# kicker.net
KiCad netlist of a schematic drawn in EAGLE
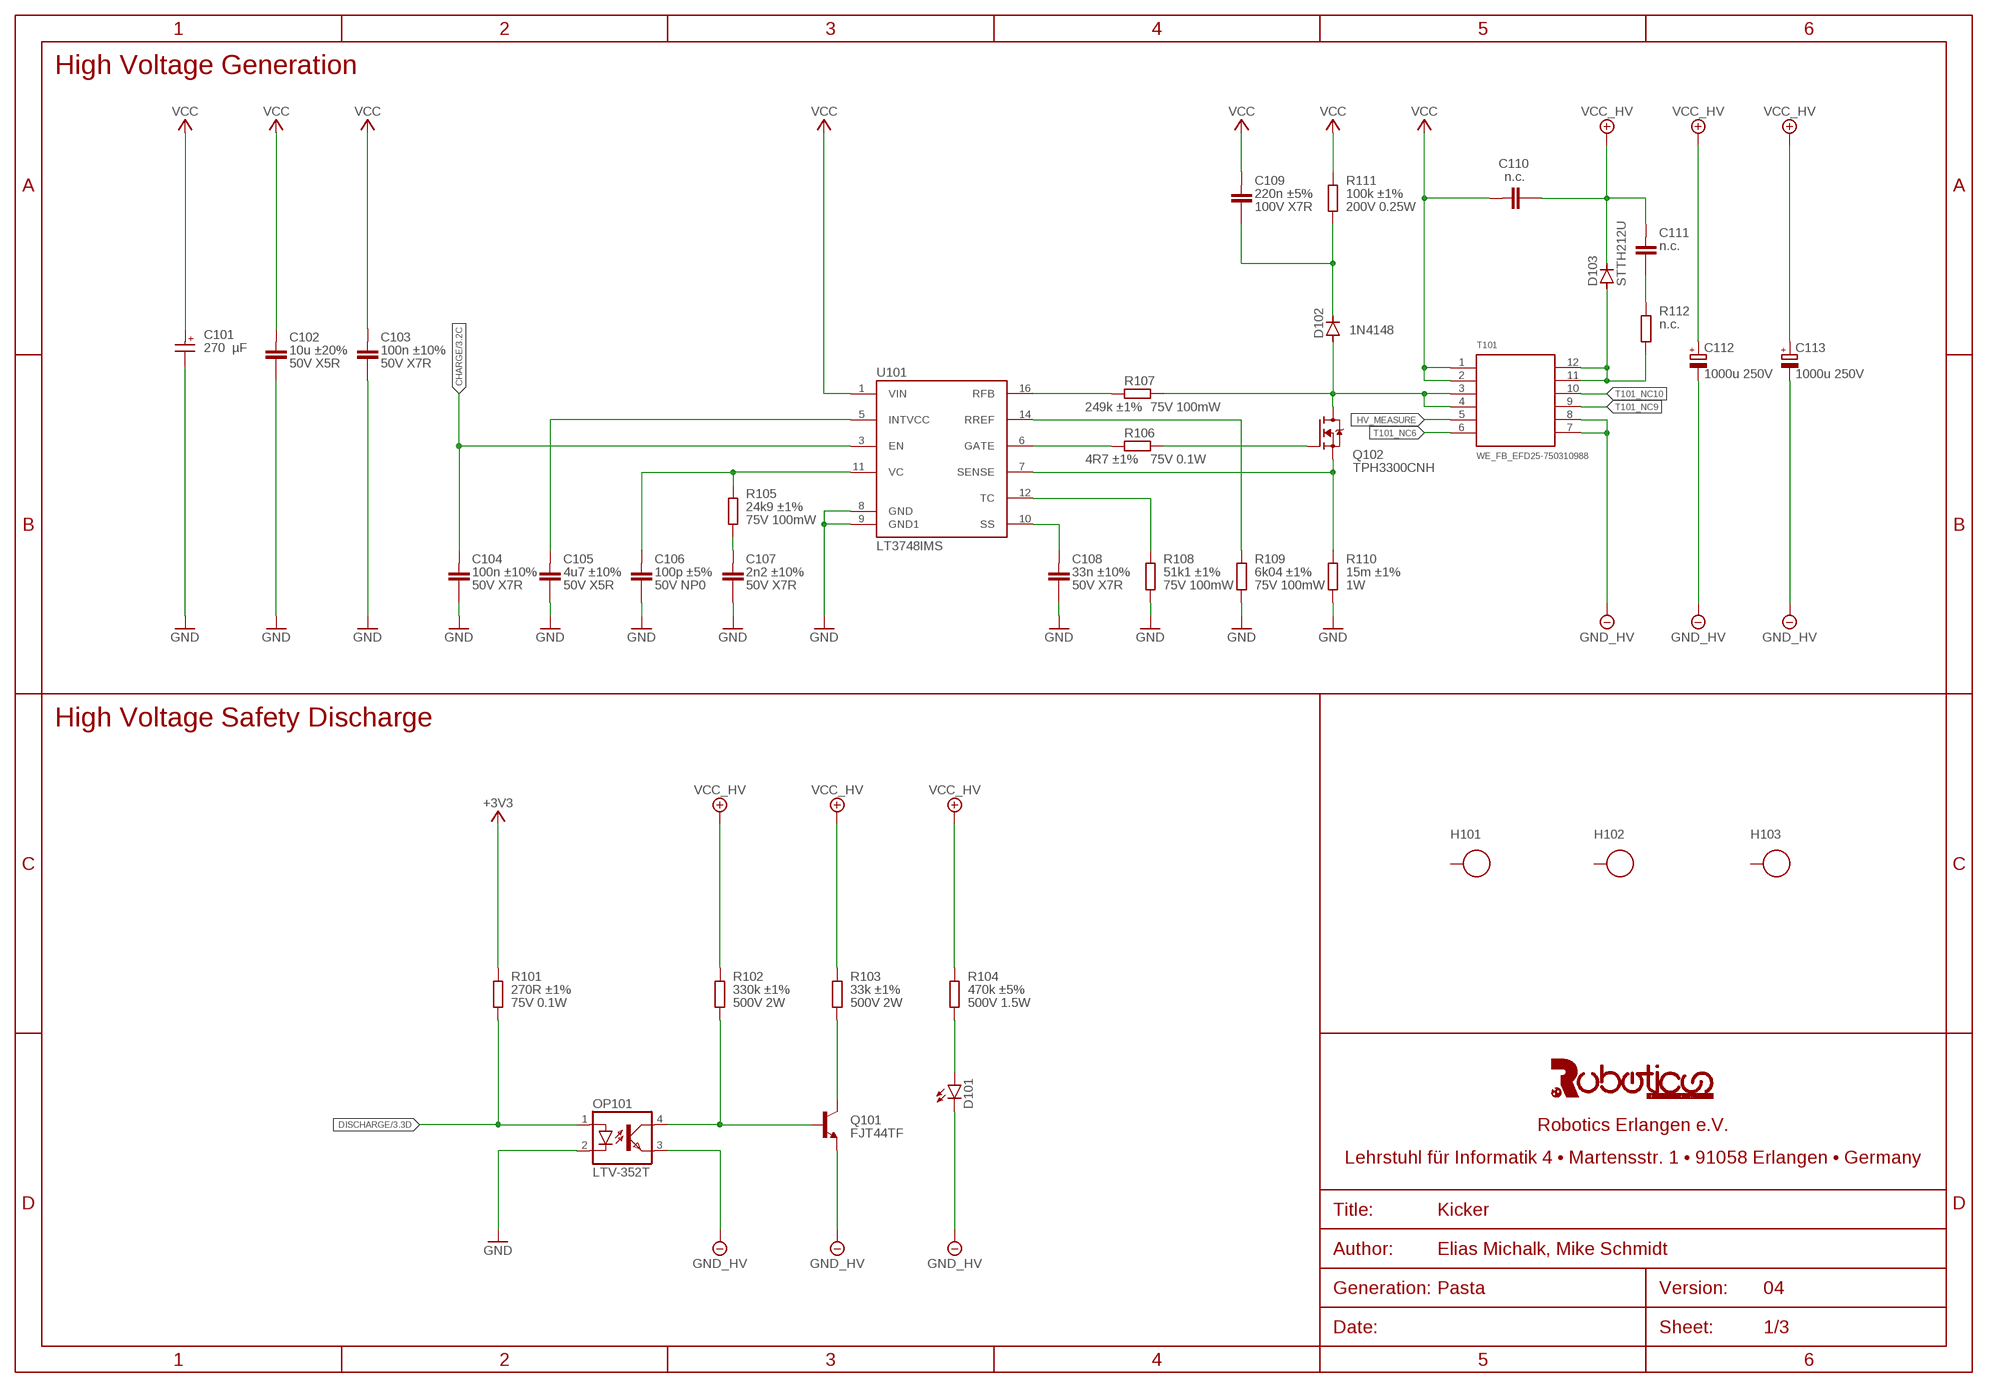
[diagram p0: schematic, sheet 1]
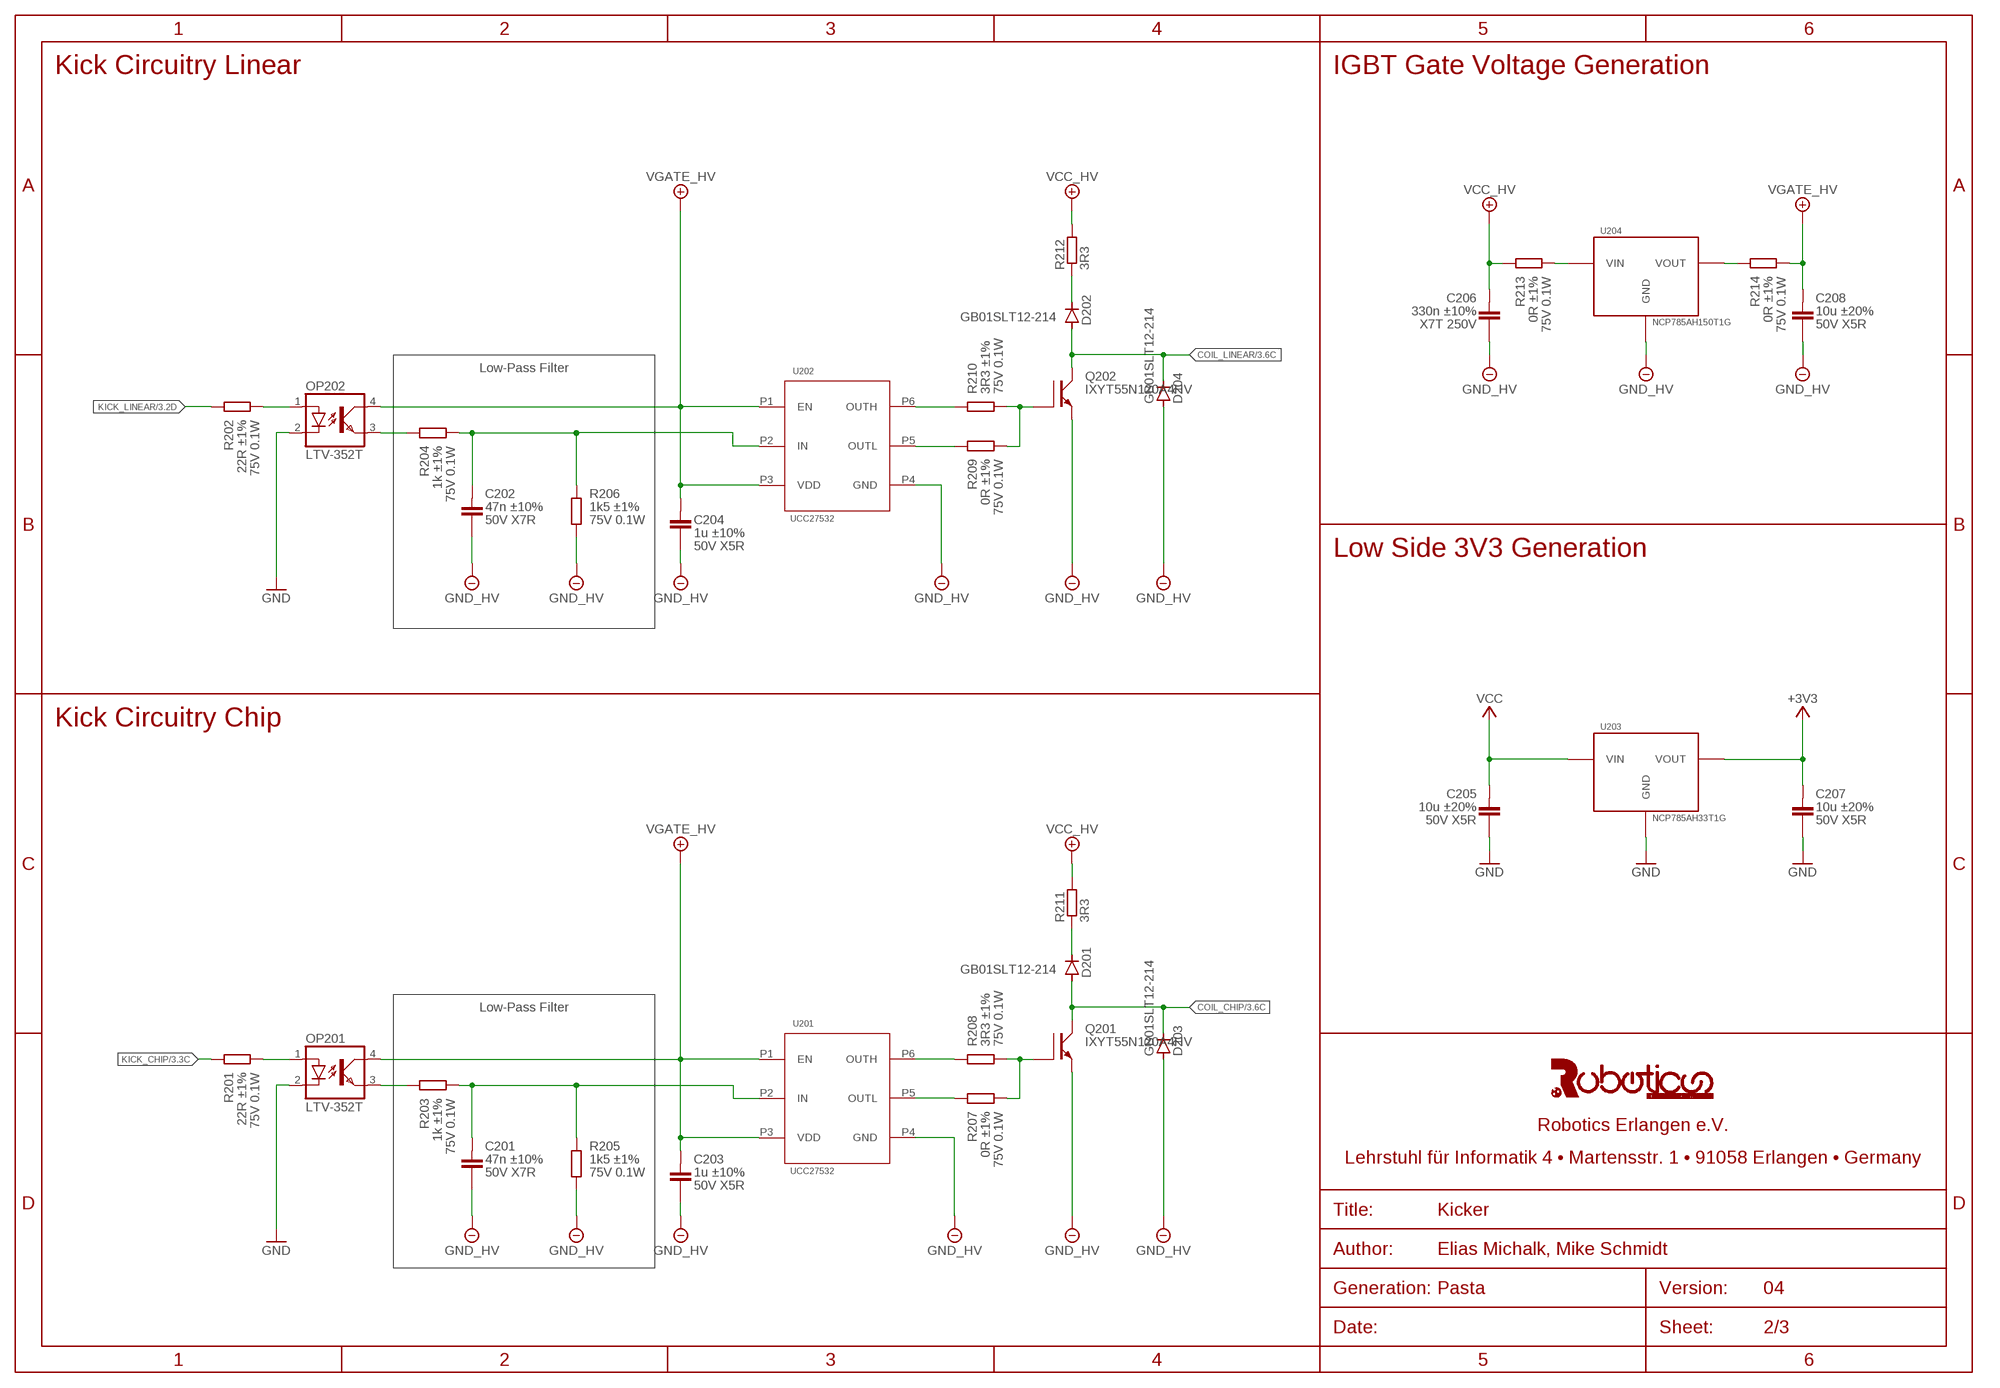
[diagram p1: schematic, sheet 2]
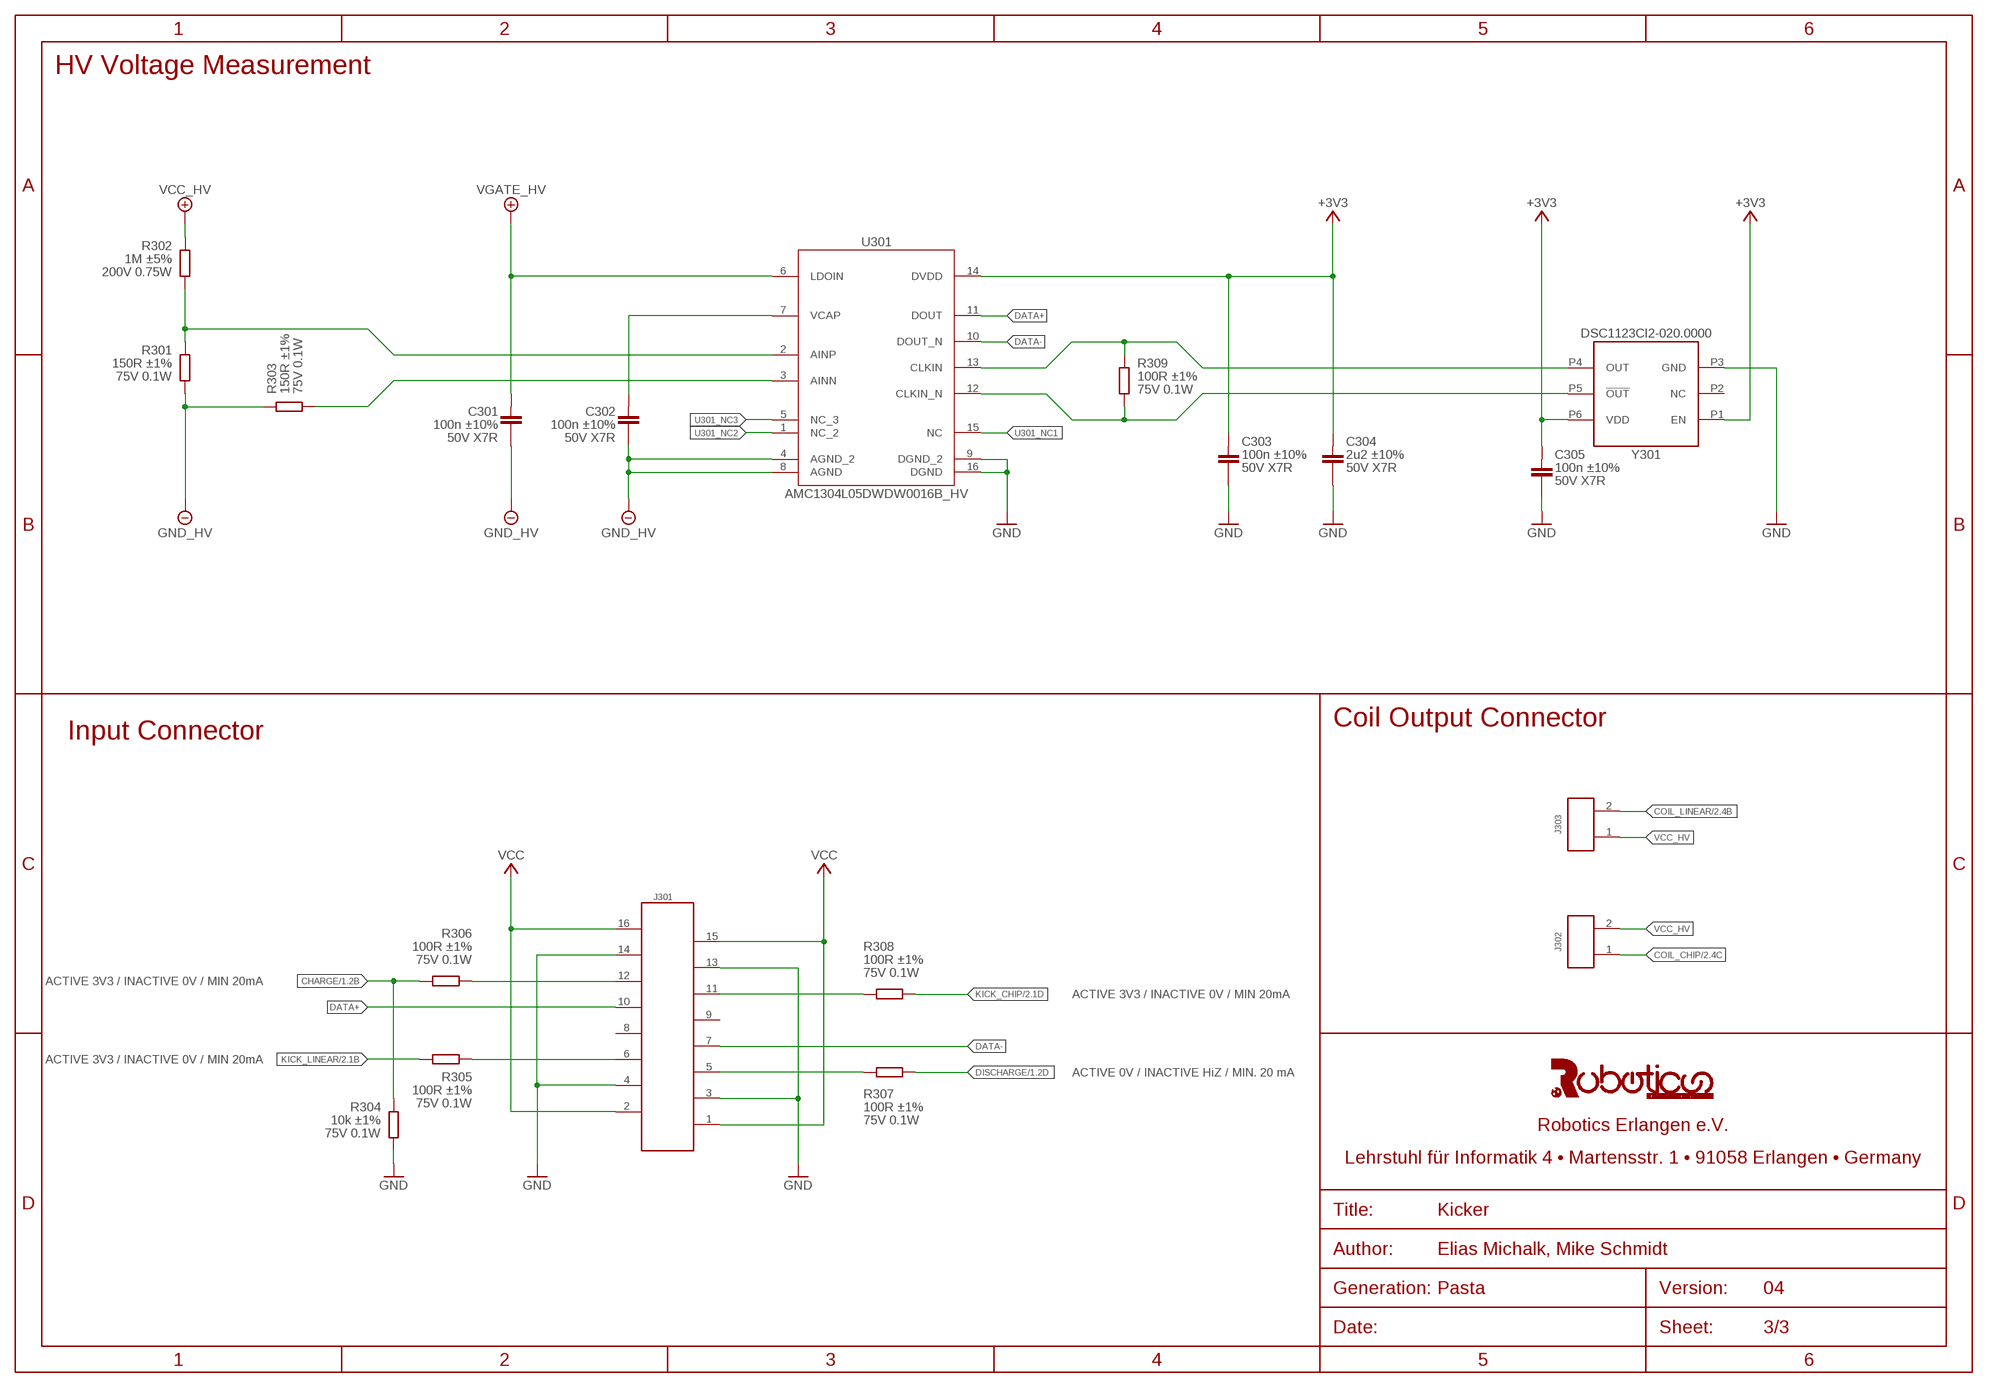
[diagram p2: schematic, sheet 3]

(export (version "E")
  (design (tool "Eeschema 10.0.6"))
  (components
    (comp (ref "C101")
      (value "270 µF")
      (footprint "eagle-import:WCAP-PSLC_10X12.4(DXL)")
      (fields
        (field (name "MF") "Würth Elektronik")
        (field (name "MPN") "875075661009 ")
        (field (name "TOLERANCE") "±10%")
      )
      (libsource (lib "eagle-import") (part "WCAP-PSLC_10X12.4_875075661009"))
    )
    (comp (ref "C102")
      (value "10u ±20% 50V X5R")
      (footprint "eagle-import:C1206")
      (fields
        (field (name "LINE1") "10u ±20%")
        (field (name "LINE2") "50V X5R")
        (field (name "MF") "Samsung")
        (field (name "MPN") "CL31A106MBHNNNE")
        (field (name "TOLERANCE") "±20%")
      )
      (libsource (lib "eagle-import") (part "C(?)120610UF,50V,"))
    )
    (comp (ref "C103")
      (value "100n ±10% 50V X7R")
      (footprint "eagle-import:C0603")
      (fields
        (field (name "LINE1") "100n ±10%")
        (field (name "LINE2") "50V X7R")
        (field (name "MF") "Würth Elektronik")
        (field (name "MPN") "885012206095")
        (field (name "TOLERANCE") "±10%")
      )
      (libsource (lib "eagle-import") (part "C(?)0603100NF,50V,"))
    )
    (comp (ref "C104")
      (value "100n ±10% 50V X7R")
      (footprint "eagle-import:C0603")
      (fields
        (field (name "LINE1") "100n ±10%")
        (field (name "LINE2") "50V X7R")
        (field (name "MF") "Würth Elektronik")
        (field (name "MPN") "885012206095")
        (field (name "TOLERANCE") "±10%")
      )
      (libsource (lib "eagle-import") (part "C(?)0603100NF,50V,"))
    )
    (comp (ref "C105")
      (value "4u7 ±10% 50V X5R")
      (footprint "eagle-import:C0805")
      (fields
        (field (name "LINE1") "4u7 ±10%")
        (field (name "LINE2") "50V X5R")
        (field (name "MF") "Samsung")
        (field (name "MPN") "CL21A475KBQNNNE")
        (field (name "TOLERANCE") "±10%")
      )
      (libsource (lib "eagle-import") (part "C(?)08054.7UF,50V,"))
    )
    (comp (ref "C106")
      (value "100p ±5% 50V NP0")
      (footprint "eagle-import:C0603")
      (fields
        (field (name "LINE1") "100p ±5%")
        (field (name "LINE2") "50V NP0")
        (field (name "MF") "Würth Elektronik")
        (field (name "MPN") "885012006057")
        (field (name "TOLERANCE") "±5%")
      )
      (libsource (lib "eagle-import") (part "C(?)0603100PF,50V,"))
    )
    (comp (ref "C107")
      (value "2n2 ±10% 50V X7R")
      (footprint "eagle-import:C0603")
      (fields
        (field (name "LINE1") "2n2 ±10%")
        (field (name "LINE2") "50V X7R")
        (field (name "MF") "Würth Elektronik")
        (field (name "MPN") "885012206085")
        (field (name "TOLERANCE") "±10%")
      )
      (libsource (lib "eagle-import") (part "C(?)06032.2NF,50V,"))
    )
    (comp (ref "C108")
      (value "33n ±10% 50V X7R")
      (footprint "eagle-import:C0603")
      (fields
        (field (name "LINE1") "33n ±10%")
        (field (name "LINE2") "50V X7R")
        (field (name "MF") "Würth Elektronik")
        (field (name "MPN") "885012206092")
        (field (name "TOLERANCE") "±10%")
      )
      (libsource (lib "eagle-import") (part "C(?)060333NF,50V,"))
    )
    (comp (ref "C109")
      (value "C(1210)")
      (footprint "eagle-import:C1210")
      (fields
        (field (name "CAPACITANCE") "220nF")
        (field (name "DIELECTRIC") "X7R")
        (field (name "LINE1") "220n ±5%")
        (field (name "LINE2") "100V X7R")
        (field (name "MF") "KEMET")
        (field (name "MPN") "C0805C224J1RECTU")
        (field (name "TOLERANCE") "±5%")
        (field (name "VOLTAGE") "100V")
      )
      (libsource (lib "eagle-import") (part "C(?)1210"))
    )
    (comp (ref "C110")
      (value "n.c.")
      (footprint "eagle-import:C1206")
      (fields (field (name "LINE1") "n.c. "))
      (libsource (lib "eagle-import") (part "C(?)1206N.C.,"))
    )
    (comp (ref "C111")
      (value "n.c.")
      (footprint "eagle-import:C1206")
      (fields (field (name "LINE1") "n.c. "))
      (libsource (lib "eagle-import") (part "C(?)1206N.C.,"))
    )
    (comp (ref "C112")
      (value "1000u 250V")
      (footprint "eagle-import:ESMQ251VSN102MQ45S")
      (fields (field (name "MF") "United Chemi-Con") (field (name "MPN") "ESMQ251VSN102MQ45S"))
      (libsource (lib "eagle-import") (part "ESMQ251VSN102MQ45S"))
    )
    (comp (ref "C113")
      (value "1000u 250V")
      (footprint "eagle-import:ESMQ251VSN102MQ45S")
      (fields (field (name "MF") "United Chemi-Con") (field (name "MPN") "ESMQ251VSN102MQ45S"))
      (libsource (lib "eagle-import") (part "ESMQ251VSN102MQ45S"))
    )
    (comp (ref "D101")
      (value "LED5MM")
      (footprint "eagle-import:LED5MM")
      (fields (field (name "MF") "Würth Elektronik") (field (name "MPN") "151054RS03000 "))
      (libsource (lib "eagle-import") (part "LED5MM"))
    )
    (comp (ref "D102")
      (value "1N4148")
      (footprint "eagle-import:SOD-123")
      (fields (field (name "MF") "Micro Commercial Components") (field (name "MPN") "1N4148W"))
      (libsource (lib "eagle-import") (part "1N4148W"))
    )
    (comp (ref "D103")
      (value "STTH212U")
      (footprint "eagle-import:SMB")
      (fields (field (name "MF") "STMicroelectronics"))
      (libsource (lib "eagle-import") (part "STTH212U"))
    )
    (comp (ref "H101")
      (value "9774060360R")
      (footprint "eagle-import:9774___360")
      (fields (field (name "MF") "Würth Elektronik"))
      (libsource (lib "eagle-import") (part "9774360R060"))
    )
    (comp (ref "H102")
      (value "9774060360R")
      (footprint "eagle-import:9774___360")
      (fields (field (name "MF") "Würth Elektronik"))
      (libsource (lib "eagle-import") (part "9774360R060"))
    )
    (comp (ref "H103")
      (value "9774060360R")
      (footprint "eagle-import:9774___360")
      (fields (field (name "MF") "Würth Elektronik"))
      (libsource (lib "eagle-import") (part "9774360R060"))
    )
    (comp (ref "OP101")
      (value "LTV-352T")
      (footprint "eagle-import:DIL4-SMD")
      (fields (field (name "MF") "Lite-On"))
      (libsource (lib "eagle-import") (part "LTV-352T"))
    )
    (comp (ref "Q101")
      (value "FJT44TF")
      (footprint "eagle-import:SOT223")
      (fields (field (name "MF") "onsemi / Fairchild"))
      (libsource (lib "eagle-import") (part "TRANSISTOR_NPN{dblquote}"))
    )
    (comp (ref "Q102")
      (value "TPH3300CNH")
      (footprint "eagle-import:SOP-8")
      (fields (field (name "MF") "Toshiba"))
      (libsource (lib "eagle-import") (part "TPH3300CNH"))
    )
    (comp (ref "R101")
      (value "270R ±1% 75V 0.1W")
      (footprint "eagle-import:R0603")
      (fields
        (field (name "LINE1") "270R ±1%")
        (field (name "LINE2") "75V 0.1W")
        (field (name "MF") "YAGEO")
        (field (name "MPN") "RC0603FR-07270RL")
        (field (name "POWER") "0.1W")
      )
      (libsource (lib "eagle-import") (part "R(?)0603270R,75V,0.1W,"))
    )
    (comp (ref "R102")
      (value "R(2512)")
      (footprint "eagle-import:R2512")
      (fields
        (field (name "LINE1") "330k ±1%")
        (field (name "LINE2") "500V 2W")
        (field (name "MF") "TE Connectivity / Holsworthy")
        (field (name "MPN") "CRGP2512F330K")
        (field (name "POWER") "2W")
        (field (name "RESISTANCE") "330k")
        (field (name "TOLERANCE") "±1%")
        (field (name "VOLTAGE") "500V")
      )
      (libsource (lib "eagle-import") (part "R(?)2512"))
    )
    (comp (ref "R103")
      (value "R(2512)")
      (footprint "eagle-import:R2512")
      (fields
        (field (name "LINE1") "33k ±1%")
        (field (name "LINE2") "500V 2W")
        (field (name "MF") "TE Connectivity / Holsworthy")
        (field (name "MPN") "CRGP2512F33K")
        (field (name "POWER") "2W")
        (field (name "RESISTANCE") "33k")
        (field (name "TOLERANCE") "1%")
        (field (name "VOLTAGE") "500V")
      )
      (libsource (lib "eagle-import") (part "R(?)2512"))
    )
    (comp (ref "R104")
      (value "R(2512)")
      (footprint "eagle-import:R2512")
      (fields
        (field (name "LINE1") "470k ±5%")
        (field (name "LINE2") "500V 1.5W")
        (field (name "MF") "Vishay / Dale")
        (field (name "MPN") "CRCW2512470KJNEGHP")
        (field (name "POWER") "1.5W")
        (field (name "RESISTANCE") "470k")
        (field (name "TOLERANCE") "±5%")
        (field (name "VOLTAGE") "500V")
      )
      (libsource (lib "eagle-import") (part "R(?)2512"))
    )
    (comp (ref "R105")
      (value "R(0603)")
      (footprint "eagle-import:R0603")
      (fields
        (field (name "LINE1") "24k9 ±1%")
        (field (name "LINE2") "75V 100mW")
        (field (name "MF") "YAGEO")
        (field (name "MPN") "RE0603FRE0724K9L")
        (field (name "POWER") "100mW")
        (field (name "RESISTANCE") "24k9")
        (field (name "TOLERANCE") "±1%")
        (field (name "VOLTAGE") "75V")
      )
      (libsource (lib "eagle-import") (part "R(?)0603"))
    )
    (comp (ref "R106")
      (value "4R7 ±1% 75V 0.1W")
      (footprint "eagle-import:R0603")
      (fields
        (field (name "LINE1") "4R7 ±1%")
        (field (name "LINE2") "75V 0.1W")
        (field (name "MF") "YAGEO")
        (field (name "MPN") "RC0603FR-074R7L")
        (field (name "POWER") "0.1W")
      )
      (libsource (lib "eagle-import") (part "R(?)06034.7R,75V,0.1W,"))
    )
    (comp (ref "R107")
      (value "R(0603)")
      (footprint "eagle-import:R0603")
      (fields
        (field (name "LINE1") "249k ±1%")
        (field (name "LINE2") "75V 100mW")
        (field (name "MF") "YAGEO")
        (field (name "MPN") "RC0603FR-07249KL")
        (field (name "POWER") "100mW")
        (field (name "RESISTANCE") "249k")
        (field (name "TOLERANCE") "±1%")
        (field (name "VOLTAGE") "75V")
      )
      (libsource (lib "eagle-import") (part "R(?)0603"))
    )
    (comp (ref "R108")
      (value "R(0603)")
      (footprint "eagle-import:R0603")
      (fields
        (field (name "LINE1") "51k1 ±1%")
        (field (name "LINE2") "75V 100mW")
        (field (name "MF") "YAGEO")
        (field (name "MPN") "RC0603FR-0751K1L")
        (field (name "POWER") "100mW")
        (field (name "RESISTANCE") "51k1")
        (field (name "TOLERANCE") "±1%")
        (field (name "VOLTAGE") "75V")
      )
      (libsource (lib "eagle-import") (part "R(?)0603"))
    )
    (comp (ref "R109")
      (value "R(0603)")
      (footprint "eagle-import:R0603")
      (fields
        (field (name "LINE1") "6k04 ±1%")
        (field (name "LINE2") "75V 100mW")
        (field (name "MF") "YAGEO")
        (field (name "MPN") "AC0603FR-136K04L")
        (field (name "POWER") "100mW")
        (field (name "RESISTANCE") "6k04")
        (field (name "TOLERANCE") "±1%")
        (field (name "VOLTAGE") "75V")
      )
      (libsource (lib "eagle-import") (part "R(?)0603"))
    )
    (comp (ref "R110")
      (value "R(1206)")
      (footprint "eagle-import:R1206")
      (fields
        (field (name "LINE1") "15m ±1%")
        (field (name "LINE2") "1W")
        (field (name "MF") "Panasonic")
        (field (name "MPN") "ERJ-8BWFR015V")
        (field (name "POWER") "1W")
        (field (name "RESISTANCE") "15m")
        (field (name "TOLERANCE") "±1%")
      )
      (libsource (lib "eagle-import") (part "R(?)1206"))
    )
    (comp (ref "R111")
      (value "100k ±1% 200V 0.25W")
      (footprint "eagle-import:R1206")
      (fields
        (field (name "LINE1") "100k ±1%")
        (field (name "LINE2") "200V 0.25W")
        (field (name "MF") "YAGEO")
        (field (name "MPN") "RC1206FR-07100KL")
        (field (name "POWER") "0.25W")
      )
      (libsource (lib "eagle-import") (part "R(?)1206100K,200V,0.25W,"))
    )
    (comp (ref "R112")
      (value "n.c.")
      (footprint "eagle-import:R1206")
      (fields (field (name "LINE1") "n.c. "))
      (libsource (lib "eagle-import") (part "R(?)1206N.C.,"))
    )
    (comp (ref "T101")
      (value "WE_FB_EFD25-750310988")
      (footprint "eagle-import:WE_FB_EFD25")
      (fields (field (name "MF") "Würth Elektronik") (field (name "MPN") "750310988"))
      (libsource (lib "eagle-import") (part "WE_FB_EFD25-750310988"))
    )
    (comp (ref "U101")
      (value "LT3748IMS")
      (footprint "eagle-import:MSOP16")
      (fields (field (name "MF") "Analog Devices") (field (name "MPN") "LT3748IMS#PBF"))
      (libsource (lib "eagle-import") (part "LT3748IMS"))
    )
    (comp (ref "C201")
      (value "47n ±10% 50V X7R")
      (footprint "eagle-import:C0603")
      (fields
        (field (name "LINE1") "47n ±10%")
        (field (name "LINE2") "50V X7R")
        (field (name "MF") "Würth Elektronik")
        (field (name "MPN") "885012206093")
        (field (name "TOLERANCE") "±10%")
      )
      (libsource (lib "eagle-import") (part "C(?)060347NF,50V,"))
    )
    (comp (ref "C202")
      (value "47n ±10% 50V X7R")
      (footprint "eagle-import:C0603")
      (fields
        (field (name "LINE1") "47n ±10%")
        (field (name "LINE2") "50V X7R")
        (field (name "MF") "Würth Elektronik")
        (field (name "MPN") "885012206093")
        (field (name "TOLERANCE") "±10%")
      )
      (libsource (lib "eagle-import") (part "C(?)060347NF,50V,"))
    )
    (comp (ref "C203")
      (value "1u ±10% 50V X5R")
      (footprint "eagle-import:C0603")
      (fields
        (field (name "LINE1") "1u ±10%")
        (field (name "LINE2") "50V X5R")
        (field (name "MF") "Samsung")
        (field (name "MPN") "CL10A105KB8NNNC")
        (field (name "TOLERANCE") "±10%")
      )
      (libsource (lib "eagle-import") (part "C(?)06031.0UF,50V,"))
    )
    (comp (ref "C204")
      (value "1u ±10% 50V X5R")
      (footprint "eagle-import:C0603")
      (fields
        (field (name "LINE1") "1u ±10%")
        (field (name "LINE2") "50V X5R")
        (field (name "MF") "Samsung")
        (field (name "MPN") "CL10A105KB8NNNC")
        (field (name "TOLERANCE") "±10%")
      )
      (libsource (lib "eagle-import") (part "C(?)06031.0UF,50V,"))
    )
    (comp (ref "C205")
      (value "10u ±20% 50V X5R")
      (footprint "eagle-import:C1206")
      (fields
        (field (name "LINE1") "10u ±20%")
        (field (name "LINE2") "50V X5R")
        (field (name "MF") "Samsung")
        (field (name "MPN") "CL31A106MBHNNNE")
        (field (name "TOLERANCE") "±20%")
      )
      (libsource (lib "eagle-import") (part "C(?)120610UF,50V,"))
    )
    (comp (ref "C206")
      (value "C(1210)")
      (footprint "eagle-import:C1210")
      (fields
        (field (name "CAPACITANCE") "330n")
        (field (name "DIELECTRIC") "X7T")
        (field (name "LINE1") "330n ±10%")
        (field (name "LINE2") "X7T 250V")
        (field (name "MF") "TDK")
        (field (name "MPN") "C3225X7T2E334K200AA")
        (field (name "TOLERANCE") "±10%")
        (field (name "VOLTAGE") "250V")
      )
      (libsource (lib "eagle-import") (part "C(?)1210"))
    )
    (comp (ref "C207")
      (value "10u ±20% 50V X5R")
      (footprint "eagle-import:C1206")
      (fields
        (field (name "LINE1") "10u ±20%")
        (field (name "LINE2") "50V X5R")
        (field (name "MF") "Samsung")
        (field (name "MPN") "CL31A106MBHNNNE")
        (field (name "TOLERANCE") "±20%")
      )
      (libsource (lib "eagle-import") (part "C(?)120610UF,50V,"))
    )
    (comp (ref "C208")
      (value "10u ±20% 50V X5R")
      (footprint "eagle-import:C1206")
      (fields
        (field (name "LINE1") "10u ±20%")
        (field (name "LINE2") "50V X5R")
        (field (name "MF") "Samsung")
        (field (name "MPN") "CL31A106MBHNNNE")
        (field (name "TOLERANCE") "±20%")
      )
      (libsource (lib "eagle-import") (part "C(?)120610UF,50V,"))
    )
    (comp (ref "D201")
      (value "GB01SLT12-214")
      (footprint "eagle-import:DO-214")
      (fields (field (name "MF") "GeneSiC") (field (name "MPN") "GB01SLT06-214"))
      (libsource (lib "eagle-import") (part "GB01SLT12-214"))
    )
    (comp (ref "D202")
      (value "GB01SLT12-214")
      (footprint "eagle-import:DO-214")
      (fields (field (name "MF") "GeneSiC") (field (name "MPN") "GB01SLT06-214"))
      (libsource (lib "eagle-import") (part "GB01SLT12-214"))
    )
    (comp (ref "D203")
      (value "GB01SLT12-214")
      (footprint "eagle-import:DO-214")
      (fields (field (name "MF") "GeneSiC") (field (name "MPN") "GB01SLT06-214"))
      (libsource (lib "eagle-import") (part "GB01SLT12-214"))
    )
    (comp (ref "D204")
      (value "GB01SLT12-214")
      (footprint "eagle-import:DO-214")
      (fields (field (name "MF") "GeneSiC") (field (name "MPN") "GB01SLT06-214"))
      (libsource (lib "eagle-import") (part "GB01SLT12-214"))
    )
    (comp (ref "OP201")
      (value "LTV-352T")
      (footprint "eagle-import:DIL4-SMD")
      (fields (field (name "MF") "Lite-On"))
      (libsource (lib "eagle-import") (part "LTV-352T"))
    )
    (comp (ref "OP202")
      (value "LTV-352T")
      (footprint "eagle-import:DIL4-SMD")
      (fields (field (name "MF") "Lite-On"))
      (libsource (lib "eagle-import") (part "LTV-352T"))
    )
    (comp (ref "Q201")
      (value "IXYT55N120A4HV")
      (footprint "eagle-import:TO-268HV")
      (fields (field (name "MF") "IXYS"))
      (libsource (lib "eagle-import") (part "IXYT55N120A4HV"))
    )
    (comp (ref "Q202")
      (value "IXYT55N120A4HV")
      (footprint "eagle-import:TO-268HV")
      (fields (field (name "MF") "IXYS"))
      (libsource (lib "eagle-import") (part "IXYT55N120A4HV"))
    )
    (comp (ref "R201")
      (value "22R ±1% 75V 0.1W")
      (footprint "eagle-import:R0603")
      (fields
        (field (name "LINE1") "22R ±1%")
        (field (name "LINE2") "75V 0.1W")
        (field (name "MF") "YAGEO")
        (field (name "MPN") "RC0603FR-0722RL")
        (field (name "POWER") "0.1W")
      )
      (libsource (lib "eagle-import") (part "R(?)060322R,75V,0.1W,"))
    )
    (comp (ref "R202")
      (value "22R ±1% 75V 0.1W")
      (footprint "eagle-import:R0603")
      (fields
        (field (name "LINE1") "22R ±1%")
        (field (name "LINE2") "75V 0.1W")
        (field (name "MF") "YAGEO")
        (field (name "MPN") "RC0603FR-0722RL")
        (field (name "POWER") "0.1W")
      )
      (libsource (lib "eagle-import") (part "R(?)060322R,75V,0.1W,"))
    )
    (comp (ref "R203")
      (value "1k ±1% 75V 0.1W")
      (footprint "eagle-import:R0603")
      (fields
        (field (name "LINE1") "1k ±1%")
        (field (name "LINE2") "75V 0.1W")
        (field (name "MF") "YAGEO")
        (field (name "MPN") "RC0603FR-071KL")
        (field (name "POWER") "0.1W")
      )
      (libsource (lib "eagle-import") (part "R(?)06031.0K,75V,0.1W,"))
    )
    (comp (ref "R204")
      (value "1k ±1% 75V 0.1W")
      (footprint "eagle-import:R0603")
      (fields
        (field (name "LINE1") "1k ±1%")
        (field (name "LINE2") "75V 0.1W")
        (field (name "MF") "YAGEO")
        (field (name "MPN") "RC0603FR-071KL")
        (field (name "POWER") "0.1W")
      )
      (libsource (lib "eagle-import") (part "R(?)06031.0K,75V,0.1W,"))
    )
    (comp (ref "R205")
      (value "1k5 ±1% 75V 0.1W")
      (footprint "eagle-import:R0603")
      (fields
        (field (name "LINE1") "1k5 ±1%")
        (field (name "LINE2") "75V 0.1W")
        (field (name "MF") "YAGEO")
        (field (name "MPN") "RC0603FR-071K5L")
        (field (name "POWER") "0.1W")
      )
      (libsource (lib "eagle-import") (part "R(?)06031.5K,75V,0.1W,"))
    )
    (comp (ref "R206")
      (value "1k5 ±1% 75V 0.1W")
      (footprint "eagle-import:R0603")
      (fields
        (field (name "LINE1") "1k5 ±1%")
        (field (name "LINE2") "75V 0.1W")
        (field (name "MF") "YAGEO")
        (field (name "MPN") "RC0603FR-071K5L")
        (field (name "POWER") "0.1W")
      )
      (libsource (lib "eagle-import") (part "R(?)06031.5K,75V,0.1W,"))
    )
    (comp (ref "R207")
      (value "0R ±1% 75V 0.1W")
      (footprint "eagle-import:R0603")
      (fields
        (field (name "LINE1") "0R ±1%")
        (field (name "LINE2") "75V 0.1W")
        (field (name "MF") "YAGEO")
        (field (name "MPN") "RC0603FR-070RL")
        (field (name "POWER") "0.1W")
      )
      (libsource (lib "eagle-import") (part "R(?)06030R,75V,0.1W,"))
    )
    (comp (ref "R208")
      (value "3R3 ±1% 75V 0.1W")
      (footprint "eagle-import:R0603")
      (fields
        (field (name "LINE1") "3R3 ±1%")
        (field (name "LINE2") "75V 0.1W")
        (field (name "MF") "YAGEO")
        (field (name "MPN") "RC0603FR-073R3L")
        (field (name "POWER") "0.1W")
      )
      (libsource (lib "eagle-import") (part "R(?)06033.3R,75V,0.1W,"))
    )
    (comp (ref "R209")
      (value "0R ±1% 75V 0.1W")
      (footprint "eagle-import:R0603")
      (fields
        (field (name "LINE1") "0R ±1%")
        (field (name "LINE2") "75V 0.1W")
        (field (name "MF") "YAGEO")
        (field (name "MPN") "RC0603FR-070RL")
        (field (name "POWER") "0.1W")
      )
      (libsource (lib "eagle-import") (part "R(?)06030R,75V,0.1W,"))
    )
    (comp (ref "R210")
      (value "3R3 ±1% 75V 0.1W")
      (footprint "eagle-import:R0603")
      (fields
        (field (name "LINE1") "3R3 ±1%")
        (field (name "LINE2") "75V 0.1W")
        (field (name "MF") "YAGEO")
        (field (name "MPN") "RC0603FR-073R3L")
        (field (name "POWER") "0.1W")
      )
      (libsource (lib "eagle-import") (part "R(?)06033.3R,75V,0.1W,"))
    )
    (comp (ref "R211")
      (value "3R3")
      (footprint "eagle-import:R4527")
      (fields (field (name "MF") "TE Connectivity / Holsworthy") (field (name "MPN") "35603R3JT"))
      (libsource (lib "eagle-import") (part "R-EU_R45273R3-"))
    )
    (comp (ref "R212")
      (value "3R3")
      (footprint "eagle-import:R4527")
      (fields (field (name "MF") "TE Connectivity / Holsworthy") (field (name "MPN") "35603R3JT"))
      (libsource (lib "eagle-import") (part "R-EU_R45273R3-"))
    )
    (comp (ref "R213")
      (value "0R ±1% 75V 0.1W")
      (footprint "eagle-import:R0603")
      (fields
        (field (name "LINE1") "0R ±1%")
        (field (name "LINE2") "75V 0.1W")
        (field (name "MF") "YAGEO")
        (field (name "MPN") "RC0603FR-070RL")
        (field (name "POWER") "0.1W")
      )
      (libsource (lib "eagle-import") (part "R(?)06030R,75V,0.1W,"))
    )
    (comp (ref "R214")
      (value "0R ±1% 75V 0.1W")
      (footprint "eagle-import:R0603")
      (fields
        (field (name "LINE1") "0R ±1%")
        (field (name "LINE2") "75V 0.1W")
        (field (name "MF") "YAGEO")
        (field (name "MPN") "RC0603FR-070RL")
        (field (name "POWER") "0.1W")
      )
      (libsource (lib "eagle-import") (part "R(?)06030R,75V,0.1W,"))
    )
    (comp (ref "U201")
      (value "UCC27532")
      (footprint "eagle-import:SOT23-6")
      (fields (field (name "MF") "Texas Instruments") (field (name "MPN") "UCC27532DBVT"))
      (libsource (lib "eagle-import") (part "UCC27532"))
    )
    (comp (ref "U202")
      (value "UCC27532")
      (footprint "eagle-import:SOT23-6")
      (fields (field (name "MF") "Texas Instruments") (field (name "MPN") "UCC27532DBVT"))
      (libsource (lib "eagle-import") (part "UCC27532"))
    )
    (comp (ref "U203")
      (value "NCP785AH33T1G")
      (footprint "eagle-import:NCP785AH_T1G")
      (fields (field (name "MF") "ON Semiconductor"))
      (libsource (lib "eagle-import") (part "NCP785AHT1G33"))
    )
    (comp (ref "U204")
      (value "NCP785AH150T1G")
      (footprint "eagle-import:NCP785AH_T1G")
      (fields (field (name "MF") "ON Semiconductor"))
      (libsource (lib "eagle-import") (part "NCP785AHT1G150"))
    )
    (comp (ref "C301")
      (value "100n ±10% 50V X7R")
      (footprint "eagle-import:C0603")
      (fields
        (field (name "LINE1") "100n ±10%")
        (field (name "LINE2") "50V X7R")
        (field (name "MF") "Würth Elektronik")
        (field (name "MPN") "885012206095")
        (field (name "TOLERANCE") "±10%")
      )
      (libsource (lib "eagle-import") (part "C(?)0603100NF,50V,"))
    )
    (comp (ref "C302")
      (value "100n ±10% 50V X7R")
      (footprint "eagle-import:C0603")
      (fields
        (field (name "LINE1") "100n ±10%")
        (field (name "LINE2") "50V X7R")
        (field (name "MF") "Würth Elektronik")
        (field (name "MPN") "885012206095")
        (field (name "TOLERANCE") "±10%")
      )
      (libsource (lib "eagle-import") (part "C(?)0603100NF,50V,"))
    )
    (comp (ref "C303")
      (value "100n ±10% 50V X7R")
      (footprint "eagle-import:C0603")
      (fields
        (field (name "LINE1") "100n ±10%")
        (field (name "LINE2") "50V X7R")
        (field (name "MF") "Würth Elektronik")
        (field (name "MPN") "885012206095")
        (field (name "TOLERANCE") "±10%")
      )
      (libsource (lib "eagle-import") (part "C(?)0603100NF,50V,"))
    )
    (comp (ref "C304")
      (value "2u2 ±10% 50V X7R")
      (footprint "eagle-import:C0805")
      (fields
        (field (name "LINE1") "2u2 ±10%")
        (field (name "LINE2") "50V X7R")
        (field (name "MF") "Samsung")
        (field (name "MPN") "CL21B225KBYNNWE")
        (field (name "TOLERANCE") "±10%")
      )
      (libsource (lib "eagle-import") (part "C(?)08052.2UF,50V,"))
    )
    (comp (ref "C305")
      (value "100n ±10% 50V X7R")
      (footprint "eagle-import:C0603")
      (fields
        (field (name "LINE1") "100n ±10%")
        (field (name "LINE2") "50V X7R")
        (field (name "MF") "Würth Elektronik")
        (field (name "MPN") "885012206095")
        (field (name "TOLERANCE") "±10%")
      )
      (libsource (lib "eagle-import") (part "C(?)0603100NF,50V,"))
    )
    (comp (ref "J301")
      (value "690367181672")
      (footprint "eagle-import:690367181672")
      (fields (field (name "MF") "Würth Elektronik"))
      (libsource (lib "eagle-import") (part "690367181672"))
    )
    (comp (ref "J302")
      (value "66100311622")
      (footprint "eagle-import:66100311622_")
      (fields (field (name "MF") "Würth Elektronik"))
      (libsource (lib "eagle-import") (part "66100311622"))
    )
    (comp (ref "J303")
      (value "66100311622")
      (footprint "eagle-import:66100311622_")
      (fields (field (name "MF") "Würth Elektronik"))
      (libsource (lib "eagle-import") (part "66100311622"))
    )
    (comp (ref "R301")
      (value "150R ±1% 75V 0.1W")
      (footprint "eagle-import:R0603")
      (fields
        (field (name "LINE1") "150R ±1%")
        (field (name "LINE2") "75V 0.1W")
        (field (name "MF") "YAGEO")
        (field (name "MPN") "RC0603FR-07150RL")
        (field (name "POWER") "0.1W")
      )
      (libsource (lib "eagle-import") (part "R(?)0603150R,75V,0.1W,"))
    )
    (comp (ref "R302")
      (value "R(2010)")
      (footprint "eagle-import:R2010")
      (fields
        (field (name "LINE1") "1M ±5%")
        (field (name "LINE2") "200V 0.75W")
        (field (name "MF") "YAGEO")
        (field (name "MPN") "RC2010JK-071ML")
        (field (name "POWER") "0.75W")
        (field (name "RESISTANCE") "1M")
        (field (name "TOLERANCE") "±5%")
        (field (name "VOLTAGE") "200V")
      )
      (libsource (lib "eagle-import") (part "R(?)2010"))
    )
    (comp (ref "R303")
      (value "150R ±1% 75V 0.1W")
      (footprint "eagle-import:R0603")
      (fields
        (field (name "LINE1") "150R ±1%")
        (field (name "LINE2") "75V 0.1W")
        (field (name "MF") "YAGEO")
        (field (name "MPN") "RC0603FR-07150RL")
        (field (name "POWER") "0.1W")
      )
      (libsource (lib "eagle-import") (part "R(?)0603150R,75V,0.1W,"))
    )
    (comp (ref "R304")
      (value "10k ±1% 75V 0.1W")
      (footprint "eagle-import:R0603")
      (fields
        (field (name "LINE1") "10k ±1%")
        (field (name "LINE2") "75V 0.1W")
        (field (name "MF") "YAGEO")
        (field (name "MPN") "RC0603FR-0710KL")
        (field (name "POWER") "0.1W")
      )
      (libsource (lib "eagle-import") (part "R(?)060310K,75V,0.1W,"))
    )
    (comp (ref "R305")
      (value "100R ±1% 75V 0.1W")
      (footprint "eagle-import:R0603")
      (fields
        (field (name "LINE1") "100R ±1%")
        (field (name "LINE2") "75V 0.1W")
        (field (name "MF") "YAGEO")
        (field (name "MPN") "RC0603FR-07100RL")
        (field (name "POWER") "0.1W")
      )
      (libsource (lib "eagle-import") (part "R(?)0603100R,75V,0.1W,"))
    )
    (comp (ref "R306")
      (value "100R ±1% 75V 0.1W")
      (footprint "eagle-import:R0603")
      (fields
        (field (name "LINE1") "100R ±1%")
        (field (name "LINE2") "75V 0.1W")
        (field (name "MF") "YAGEO")
        (field (name "MPN") "RC0603FR-07100RL")
        (field (name "POWER") "0.1W")
      )
      (libsource (lib "eagle-import") (part "R(?)0603100R,75V,0.1W,"))
    )
    (comp (ref "R307")
      (value "100R ±1% 75V 0.1W")
      (footprint "eagle-import:R0603")
      (fields
        (field (name "LINE1") "100R ±1%")
        (field (name "LINE2") "75V 0.1W")
        (field (name "MF") "YAGEO")
        (field (name "MPN") "RC0603FR-07100RL")
        (field (name "POWER") "0.1W")
      )
      (libsource (lib "eagle-import") (part "R(?)0603100R,75V,0.1W,"))
    )
    (comp (ref "R308")
      (value "100R ±1% 75V 0.1W")
      (footprint "eagle-import:R0603")
      (fields
        (field (name "LINE1") "100R ±1%")
        (field (name "LINE2") "75V 0.1W")
        (field (name "MF") "YAGEO")
        (field (name "MPN") "RC0603FR-07100RL")
        (field (name "POWER") "0.1W")
      )
      (libsource (lib "eagle-import") (part "R(?)0603100R,75V,0.1W,"))
    )
    (comp (ref "R309")
      (value "100R ±1% 75V 0.1W")
      (footprint "eagle-import:R0603")
      (fields
        (field (name "LINE1") "100R ±1%")
        (field (name "LINE2") "75V 0.1W")
        (field (name "MF") "YAGEO")
        (field (name "MPN") "RC0603FR-07100RL")
        (field (name "POWER") "0.1W")
      )
      (libsource (lib "eagle-import") (part "R(?)0603100R,75V,0.1W,"))
    )
    (comp (ref "U301")
      (value "AMC1304L05DWDW0016B_HV")
      (footprint "eagle-import:DW0016B_HV")
      (fields (field (name "MF") "Texas Instruments") (field (name "MPN") "AMC1304L05DW"))
      (libsource (lib "eagle-import") (part "AMC1304L05DWDW0016B_HV"))
    )
    (comp (ref "Y301")
      (value "DSC1123CI2-020.0000")
      (footprint "eagle-import:DSC11X3")
      (fields (field (name "MF") "Microchip Technology"))
      (libsource (lib "eagle-import") (part "DSC1123?CI2-020.0000"))
    )
  )
  (nets
    (net (code "1") (name "+3V3") (class "Default")
      (node (ref "C207") (pin "1") (pinfunction "1_1") (pintype "passive"))
      (node (ref "C303") (pin "1") (pinfunction "1_1") (pintype "passive"))
      (node (ref "C304") (pin "1") (pinfunction "1_1") (pintype "passive"))
      (node (ref "C305") (pin "1") (pinfunction "1_1") (pintype "passive"))
      (node (ref "R101") (pin "2") (pinfunction "2_2") (pintype "passive"))
      (node (ref "U203") (pin "3") (pinfunction "VOUT_3") (pintype "power_in"))
      (node (ref "U301") (pin "14") (pinfunction "DVDD_14") (pintype "power_in"))
      (node (ref "Y301") (pin "P1") (pinfunction "EN_P1") (pintype "bidirectional"))
      (node (ref "Y301") (pin "P6") (pinfunction "VDD_P6") (pintype "power_in"))
    )
    (net (code "2") (name "CHARGE") (class "Default")
      (node (ref "C104") (pin "1") (pinfunction "1_1") (pintype "passive"))
      (node (ref "R304") (pin "2") (pinfunction "2_2") (pintype "passive"))
      (node (ref "R306") (pin "2") (pinfunction "2_2") (pintype "passive"))
      (node (ref "U101") (pin "3") (pinfunction "EN_3") (pintype "bidirectional"))
    )
    (net (code "3") (name "COIL_CHIP") (class "Default")
      (node (ref "D201") (pin "A") (pinfunction "A_A") (pintype "passive"))
      (node (ref "D203") (pin "C") (pinfunction "C_C") (pintype "passive"))
      (node (ref "J302") (pin "1") (pinfunction "1_1") (pintype "passive"))
      (node (ref "Q201") (pin "3") (pinfunction "C_3") (pintype "passive"))
    )
    (net (code "4") (name "COIL_LINEAR") (class "Default")
      (node (ref "D202") (pin "A") (pinfunction "A_A") (pintype "passive"))
      (node (ref "D204") (pin "C") (pinfunction "C_C") (pintype "passive"))
      (node (ref "J303") (pin "2") (pinfunction "2_2") (pintype "passive"))
      (node (ref "Q202") (pin "3") (pinfunction "C_3") (pintype "passive"))
    )
    (net (code "5") (name "DATA+") (class "Default")
      (node (ref "J301") (pin "10") (pinfunction "7_10") (pintype "passive"))
      (node (ref "U301") (pin "11") (pinfunction "DOUT_11") (pintype "output"))
    )
    (net (code "6") (name "DATA-") (class "Default")
      (node (ref "J301") (pin "7") (pinfunction "10_7") (pintype "passive"))
      (node (ref "U301") (pin "10") (pinfunction "DOUT_N_10") (pintype "output"))
    )
    (net (code "7") (name "DISCHARGE") (class "Default")
      (node (ref "OP101") (pin "1") (pinfunction "A_1") (pintype "passive"))
      (node (ref "R101") (pin "1") (pinfunction "1_1") (pintype "passive"))
      (node (ref "R307") (pin "2") (pinfunction "2_2") (pintype "passive"))
    )
    (net (code "8") (name "GND") (class "Default")
      (node (ref "C101") (pin "2") (pinfunction "-_2") (pintype "passive"))
      (node (ref "C102") (pin "2") (pinfunction "2_2") (pintype "passive"))
      (node (ref "C103") (pin "2") (pinfunction "2_2") (pintype "passive"))
      (node (ref "C104") (pin "2") (pinfunction "2_2") (pintype "passive"))
      (node (ref "C105") (pin "2") (pinfunction "2_2") (pintype "passive"))
      (node (ref "C106") (pin "2") (pinfunction "2_2") (pintype "passive"))
      (node (ref "C107") (pin "2") (pinfunction "2_2") (pintype "passive"))
      (node (ref "C108") (pin "2") (pinfunction "2_2") (pintype "passive"))
      (node (ref "C205") (pin "2") (pinfunction "2_2") (pintype "passive"))
      (node (ref "C207") (pin "2") (pinfunction "2_2") (pintype "passive"))
      (node (ref "C303") (pin "2") (pinfunction "2_2") (pintype "passive"))
      (node (ref "C304") (pin "2") (pinfunction "2_2") (pintype "passive"))
      (node (ref "C305") (pin "2") (pinfunction "2_2") (pintype "passive"))
      (node (ref "J301") (pin "13") (pinfunction "4_13") (pintype "passive"))
      (node (ref "J301") (pin "14") (pinfunction "3_14") (pintype "passive"))
      (node (ref "J301") (pin "3") (pinfunction "14_3") (pintype "passive"))
      (node (ref "J301") (pin "4") (pinfunction "13_4") (pintype "passive"))
      (node (ref "OP101") (pin "2") (pinfunction "C_2") (pintype "passive"))
      (node (ref "OP201") (pin "2") (pinfunction "C_2") (pintype "passive"))
      (node (ref "OP202") (pin "2") (pinfunction "C_2") (pintype "passive"))
      (node (ref "R108") (pin "1") (pinfunction "1_1") (pintype "passive"))
      (node (ref "R109") (pin "1") (pinfunction "1_1") (pintype "passive"))
      (node (ref "R110") (pin "1") (pinfunction "1_1") (pintype "passive"))
      (node (ref "R304") (pin "1") (pinfunction "1_1") (pintype "passive"))
      (node (ref "U101") (pin "8") (pinfunction "GND_8") (pintype "bidirectional"))
      (node (ref "U101") (pin "9") (pinfunction "GND1_9") (pintype "bidirectional"))
      (node (ref "U203") (pin "2") (pinfunction "GND_2") (pintype "power_in"))
      (node (ref "U301") (pin "16") (pinfunction "DGND_16") (pintype "power_in"))
      (node (ref "U301") (pin "9") (pinfunction "DGND_2_9") (pintype "power_in"))
      (node (ref "Y301") (pin "P3") (pinfunction "GND_P3") (pintype "power_in"))
    )
    (net (code "9") (name "GND_HV") (class "Default")
      (node (ref "C112") (pin "N") (pinfunction "-_N") (pintype "passive"))
      (node (ref "C113") (pin "N") (pinfunction "-_N") (pintype "passive"))
      (node (ref "C201") (pin "2") (pinfunction "2_2") (pintype "passive"))
      (node (ref "C202") (pin "2") (pinfunction "2_2") (pintype "passive"))
      (node (ref "C203") (pin "2") (pinfunction "2_2") (pintype "passive"))
      (node (ref "C204") (pin "2") (pinfunction "2_2") (pintype "passive"))
      (node (ref "C206") (pin "2") (pinfunction "2_2") (pintype "passive"))
      (node (ref "C208") (pin "2") (pinfunction "2_2") (pintype "passive"))
      (node (ref "C301") (pin "2") (pinfunction "2_2") (pintype "passive"))
      (node (ref "C302") (pin "2") (pinfunction "2_2") (pintype "passive"))
      (node (ref "D101") (pin "K") (pinfunction "C_K") (pintype "passive"))
      (node (ref "D203") (pin "A") (pinfunction "A_A") (pintype "passive"))
      (node (ref "D204") (pin "A") (pinfunction "A_A") (pintype "passive"))
      (node (ref "OP101") (pin "3") (pinfunction "EMIT_3") (pintype "passive"))
      (node (ref "Q101") (pin "3") (pinfunction "E_3") (pintype "passive"))
      (node (ref "Q201") (pin "1") (pinfunction "E_1") (pintype "passive"))
      (node (ref "Q202") (pin "1") (pinfunction "E_1") (pintype "passive"))
      (node (ref "R205") (pin "1") (pinfunction "1_1") (pintype "passive"))
      (node (ref "R206") (pin "1") (pinfunction "1_1") (pintype "passive"))
      (node (ref "R301") (pin "1") (pinfunction "1_1") (pintype "passive"))
      (node (ref "R303") (pin "2") (pinfunction "2_2") (pintype "passive"))
      (node (ref "T101") (pin "7") (pinfunction "7_7") (pintype "bidirectional"))
      (node (ref "T101") (pin "8") (pinfunction "8_8") (pintype "bidirectional"))
      (node (ref "U201") (pin "P4") (pinfunction "GND_P4") (pintype "bidirectional"))
      (node (ref "U202") (pin "P4") (pinfunction "GND_P4") (pintype "bidirectional"))
      (node (ref "U204") (pin "2") (pinfunction "GND_2") (pintype "power_in"))
      (node (ref "U301") (pin "4") (pinfunction "AGND_2_4") (pintype "power_in"))
      (node (ref "U301") (pin "8") (pinfunction "AGND_8") (pintype "power_in"))
    )
    (net (code "10") (name "HV_MEASURE") (class "Default")
      (node (ref "T101") (pin "5") (pinfunction "5_5") (pintype "bidirectional"))
    )
    (net (code "11") (name "KICK_CHIP") (class "Default")
      (node (ref "R201") (pin "1") (pinfunction "1_1") (pintype "passive"))
      (node (ref "R308") (pin "1") (pinfunction "1_1") (pintype "passive"))
    )
    (net (code "12") (name "KICK_LINEAR") (class "Default")
      (node (ref "R202") (pin "1") (pinfunction "1_1") (pintype "passive"))
      (node (ref "R305") (pin "2") (pinfunction "2_2") (pintype "passive"))
    )
    (net (code "13") (name "Net-(C107-Pad1)") (class "Default")
      (node (ref "C107") (pin "1") (pinfunction "1_1") (pintype "passive"))
      (node (ref "R105") (pin "1") (pinfunction "1_1") (pintype "passive"))
    )
    (net (code "14") (name "Net-(C109-Pad2)") (class "Default")
      (node (ref "C109") (pin "2") (pinfunction "2_2") (pintype "passive"))
      (node (ref "D102") (pin "C") (pinfunction "C_C") (pintype "passive"))
      (node (ref "R111") (pin "1") (pinfunction "1_1") (pintype "passive"))
    )
    (net (code "15") (name "Net-(C111-Pad2)") (class "Default")
      (node (ref "C111") (pin "2") (pinfunction "2_2") (pintype "passive"))
      (node (ref "R112") (pin "2") (pinfunction "2_2") (pintype "passive"))
    )
    (net (code "16") (name "Net-(D101-PadA)") (class "Default")
      (node (ref "D101") (pin "A") (pinfunction "A_A") (pintype "passive"))
      (node (ref "R104") (pin "1") (pinfunction "1_1") (pintype "passive"))
    )
    (net (code "17") (name "Net-(D103-PadA)") (class "Default")
      (node (ref "D103") (pin "A") (pinfunction "A_A") (pintype "passive"))
      (node (ref "R112") (pin "1") (pinfunction "1_1") (pintype "passive"))
      (node (ref "T101") (pin "11") (pinfunction "11_11") (pintype "bidirectional"))
      (node (ref "T101") (pin "12") (pinfunction "12_12") (pintype "bidirectional"))
    )
    (net (code "18") (name "Net-(D201-PadC)") (class "Default")
      (node (ref "D201") (pin "C") (pinfunction "C_C") (pintype "passive"))
      (node (ref "R211") (pin "1") (pinfunction "1_1") (pintype "passive"))
    )
    (net (code "19") (name "Net-(D202-PadC)") (class "Default")
      (node (ref "D202") (pin "C") (pinfunction "C_C") (pintype "passive"))
      (node (ref "R212") (pin "1") (pinfunction "1_1") (pintype "passive"))
    )
    (net (code "20") (name "Net-(J301-5)") (class "Default")
      (node (ref "J301") (pin "12") (pinfunction "5_12") (pintype "passive"))
      (node (ref "R306") (pin "1") (pinfunction "1_1") (pintype "passive"))
    )
    (net (code "21") (name "Net-(J301-6)") (class "Default")
      (node (ref "J301") (pin "11") (pinfunction "6_11") (pintype "passive"))
      (node (ref "R308") (pin "2") (pinfunction "2_2") (pintype "passive"))
    )
    (net (code "22") (name "Net-(J301-11)") (class "Default")
      (node (ref "J301") (pin "6") (pinfunction "11_6") (pintype "passive"))
      (node (ref "R305") (pin "1") (pinfunction "1_1") (pintype "passive"))
    )
    (net (code "23") (name "Net-(J301-12)") (class "Default")
      (node (ref "J301") (pin "5") (pinfunction "12_5") (pintype "passive"))
      (node (ref "R307") (pin "1") (pinfunction "1_1") (pintype "passive"))
    )
    (net (code "24") (name "Net-(OP101-COL)") (class "Default")
      (node (ref "OP101") (pin "4") (pinfunction "COL_4") (pintype "passive"))
      (node (ref "Q101") (pin "1") (pinfunction "B_1") (pintype "passive"))
      (node (ref "R102") (pin "1") (pinfunction "1_1") (pintype "passive"))
    )
    (net (code "25") (name "Net-(OP201-A)") (class "Default")
      (node (ref "OP201") (pin "1") (pinfunction "A_1") (pintype "passive"))
      (node (ref "R201") (pin "2") (pinfunction "2_2") (pintype "passive"))
    )
    (net (code "26") (name "Net-(OP201-EMIT)") (class "Default")
      (node (ref "OP201") (pin "3") (pinfunction "EMIT_3") (pintype "passive"))
      (node (ref "R203") (pin "1") (pinfunction "1_1") (pintype "passive"))
    )
    (net (code "27") (name "Net-(OP202-A)") (class "Default")
      (node (ref "OP202") (pin "1") (pinfunction "A_1") (pintype "passive"))
      (node (ref "R202") (pin "2") (pinfunction "2_2") (pintype "passive"))
    )
    (net (code "28") (name "Net-(OP202-EMIT)") (class "Default")
      (node (ref "OP202") (pin "3") (pinfunction "EMIT_3") (pintype "passive"))
      (node (ref "R204") (pin "1") (pinfunction "1_1") (pintype "passive"))
    )
    (net (code "29") (name "Net-(Q101-C-Pad2)") (class "Default")
      (node (ref "Q101") (pin "2") (pinfunction "C_2") (pintype "passive"))
      (node (ref "Q101") (pin "4") (pinfunction "C_4") (pintype "passive"))
      (node (ref "R103") (pin "1") (pinfunction "1_1") (pintype "passive"))
    )
    (net (code "30") (name "Net-(Q102-D)") (class "Default")
      (node (ref "D102") (pin "A") (pinfunction "A_A") (pintype "passive"))
      (node (ref "Q102") (pin "5") (pinfunction "D_5") (pintype "passive"))
      (node (ref "R107") (pin "1") (pinfunction "1_1") (pintype "passive"))
      (node (ref "T101") (pin "3") (pinfunction "3_3") (pintype "bidirectional"))
      (node (ref "T101") (pin "4") (pinfunction "4_4") (pintype "bidirectional"))
    )
    (net (code "31") (name "Net-(Q102-G)") (class "Default")
      (node (ref "Q102") (pin "4") (pinfunction "G_4") (pintype "passive"))
      (node (ref "R106") (pin "1") (pinfunction "1_1") (pintype "passive"))
    )
    (net (code "32") (name "Net-(Q201-G)") (class "Default")
      (node (ref "Q201") (pin "2") (pinfunction "G_2") (pintype "passive"))
      (node (ref "R207") (pin "2") (pinfunction "2_2") (pintype "passive"))
      (node (ref "R208") (pin "2") (pinfunction "2_2") (pintype "passive"))
    )
    (net (code "33") (name "Net-(Q202-G)") (class "Default")
      (node (ref "Q202") (pin "2") (pinfunction "G_2") (pintype "passive"))
      (node (ref "R209") (pin "2") (pinfunction "2_2") (pintype "passive"))
      (node (ref "R210") (pin "2") (pinfunction "2_2") (pintype "passive"))
    )
    (net (code "34") (name "Net-(U101-GATE)") (class "Default")
      (node (ref "R106") (pin "2") (pinfunction "2_2") (pintype "passive"))
      (node (ref "U101") (pin "6") (pinfunction "GATE_6") (pintype "bidirectional"))
    )
    (net (code "35") (name "Net-(U101-INTVCC)") (class "Default")
      (node (ref "C105") (pin "1") (pinfunction "1_1") (pintype "passive"))
      (node (ref "U101") (pin "5") (pinfunction "INTVCC_5") (pintype "bidirectional"))
    )
    (net (code "36") (name "Net-(U101-RFB)") (class "Default")
      (node (ref "R107") (pin "2") (pinfunction "2_2") (pintype "passive"))
      (node (ref "U101") (pin "16") (pinfunction "RFB_16") (pintype "bidirectional"))
    )
    (net (code "37") (name "Net-(U101-RREF)") (class "Default")
      (node (ref "R109") (pin "2") (pinfunction "2_2") (pintype "passive"))
      (node (ref "U101") (pin "14") (pinfunction "RREF_14") (pintype "bidirectional"))
    )
    (net (code "38") (name "Net-(U101-SENSE)") (class "Default")
      (node (ref "Q102") (pin "1") (pinfunction "S_1") (pintype "passive"))
      (node (ref "Q102") (pin "2") (pinfunction "S_2") (pintype "passive"))
      (node (ref "Q102") (pin "3") (pinfunction "S_3") (pintype "passive"))
      (node (ref "R110") (pin "2") (pinfunction "2_2") (pintype "passive"))
      (node (ref "U101") (pin "7") (pinfunction "SENSE_7") (pintype "bidirectional"))
    )
    (net (code "39") (name "Net-(U101-SS)") (class "Default")
      (node (ref "C108") (pin "1") (pinfunction "1_1") (pintype "passive"))
      (node (ref "U101") (pin "10") (pinfunction "SS_10") (pintype "bidirectional"))
    )
    (net (code "40") (name "Net-(U101-TC)") (class "Default")
      (node (ref "R108") (pin "2") (pinfunction "2_2") (pintype "passive"))
      (node (ref "U101") (pin "12") (pinfunction "TC_12") (pintype "bidirectional"))
    )
    (net (code "41") (name "Net-(U101-VC)") (class "Default")
      (node (ref "C106") (pin "1") (pinfunction "1_1") (pintype "passive"))
      (node (ref "R105") (pin "2") (pinfunction "2_2") (pintype "passive"))
      (node (ref "U101") (pin "11") (pinfunction "VC_11") (pintype "bidirectional"))
    )
    (net (code "42") (name "Net-(U201-IN)") (class "Default")
      (node (ref "C201") (pin "1") (pinfunction "1_1") (pintype "passive"))
      (node (ref "R203") (pin "2") (pinfunction "2_2") (pintype "passive"))
      (node (ref "R205") (pin "2") (pinfunction "2_2") (pintype "passive"))
      (node (ref "U201") (pin "P2") (pinfunction "IN_P2") (pintype "bidirectional"))
    )
    (net (code "43") (name "Net-(U201-OUTH)") (class "Default")
      (node (ref "R208") (pin "1") (pinfunction "1_1") (pintype "passive"))
      (node (ref "U201") (pin "P6") (pinfunction "OUTH_P6") (pintype "bidirectional"))
    )
    (net (code "44") (name "Net-(U201-OUTL)") (class "Default")
      (node (ref "R207") (pin "1") (pinfunction "1_1") (pintype "passive"))
      (node (ref "U201") (pin "P5") (pinfunction "OUTL_P5") (pintype "bidirectional"))
    )
    (net (code "45") (name "Net-(U202-IN)") (class "Default")
      (node (ref "C202") (pin "1") (pinfunction "1_1") (pintype "passive"))
      (node (ref "R204") (pin "2") (pinfunction "2_2") (pintype "passive"))
      (node (ref "R206") (pin "2") (pinfunction "2_2") (pintype "passive"))
      (node (ref "U202") (pin "P2") (pinfunction "IN_P2") (pintype "bidirectional"))
    )
    (net (code "46") (name "Net-(U202-OUTH)") (class "Default")
      (node (ref "R210") (pin "1") (pinfunction "1_1") (pintype "passive"))
      (node (ref "U202") (pin "P6") (pinfunction "OUTH_P6") (pintype "bidirectional"))
    )
    (net (code "47") (name "Net-(U202-OUTL)") (class "Default")
      (node (ref "R209") (pin "1") (pinfunction "1_1") (pintype "passive"))
      (node (ref "U202") (pin "P5") (pinfunction "OUTL_P5") (pintype "bidirectional"))
    )
    (net (code "48") (name "Net-(U204-VIN)") (class "Default")
      (node (ref "R213") (pin "2") (pinfunction "2_2") (pintype "passive"))
      (node (ref "U204") (pin "1") (pinfunction "VIN_1") (pintype "power_in"))
    )
    (net (code "49") (name "Net-(U204-VOUT)") (class "Default")
      (node (ref "R214") (pin "1") (pinfunction "1_1") (pintype "passive"))
      (node (ref "U204") (pin "3") (pinfunction "VOUT_3") (pintype "power_in"))
    )
    (net (code "50") (name "Net-(U301-AINN)") (class "Default")
      (node (ref "R303") (pin "1") (pinfunction "1_1") (pintype "passive"))
      (node (ref "U301") (pin "3") (pinfunction "AINN_3") (pintype "input"))
    )
    (net (code "51") (name "Net-(U301-AINP)") (class "Default")
      (node (ref "R301") (pin "2") (pinfunction "2_2") (pintype "passive"))
      (node (ref "R302") (pin "1") (pinfunction "1_1") (pintype "passive"))
      (node (ref "U301") (pin "2") (pinfunction "AINP_2") (pintype "input"))
    )
    (net (code "52") (name "Net-(U301-CLKIN)") (class "Default")
      (node (ref "R309") (pin "2") (pinfunction "2_2") (pintype "passive"))
      (node (ref "U301") (pin "13") (pinfunction "CLKIN_13") (pintype "input"))
      (node (ref "Y301") (pin "P4") (pinfunction "OUT_P4") (pintype "output"))
    )
    (net (code "53") (name "Net-(U301-CLKIN_N)") (class "Default")
      (node (ref "R309") (pin "1") (pinfunction "1_1") (pintype "passive"))
      (node (ref "U301") (pin "12") (pinfunction "CLKIN_N_12") (pintype "input"))
      (node (ref "Y301") (pin "P5") (pinfunction "~{OUT}_P5") (pintype "output"))
    )
    (net (code "54") (name "Net-(U301-VCAP)") (class "Default")
      (node (ref "C302") (pin "1") (pinfunction "1_1") (pintype "passive"))
      (node (ref "U301") (pin "7") (pinfunction "VCAP_7") (pintype "power_in"))
    )
    (net (code "55") (name "T101_NC6") (class "Default")
      (node (ref "T101") (pin "6") (pinfunction "6_6") (pintype "bidirectional"))
    )
    (net (code "56") (name "T101_NC9") (class "Default")
      (node (ref "T101") (pin "9") (pinfunction "9_9") (pintype "bidirectional"))
    )
    (net (code "57") (name "T101_NC10") (class "Default")
      (node (ref "T101") (pin "10") (pinfunction "10_10") (pintype "bidirectional"))
    )
    (net (code "58") (name "U301_NC1") (class "Default")
      (node (ref "U301") (pin "15") (pinfunction "NC_15") (pintype "passive"))
    )
    (net (code "59") (name "U301_NC2") (class "Default")
      (node (ref "U301") (pin "1") (pinfunction "NC_2_1") (pintype "passive"))
    )
    (net (code "60") (name "U301_NC3") (class "Default")
      (node (ref "U301") (pin "5") (pinfunction "NC_3_5") (pintype "passive"))
    )
    (net (code "61") (name "VCC") (class "Default")
      (node (ref "C101") (pin "1") (pinfunction "+_1") (pintype "passive"))
      (node (ref "C102") (pin "1") (pinfunction "1_1") (pintype "passive"))
      (node (ref "C103") (pin "1") (pinfunction "1_1") (pintype "passive"))
      (node (ref "C109") (pin "1") (pinfunction "1_1") (pintype "passive"))
      (node (ref "C110") (pin "1") (pinfunction "1_1") (pintype "passive"))
      (node (ref "C205") (pin "1") (pinfunction "1_1") (pintype "passive"))
      (node (ref "J301") (pin "1") (pinfunction "16_1") (pintype "passive"))
      (node (ref "J301") (pin "15") (pinfunction "2_15") (pintype "passive"))
      (node (ref "J301") (pin "16") (pinfunction "1_16") (pintype "passive"))
      (node (ref "J301") (pin "2") (pinfunction "15_2") (pintype "passive"))
      (node (ref "R111") (pin "2") (pinfunction "2_2") (pintype "passive"))
      (node (ref "T101") (pin "1") (pinfunction "1_1") (pintype "bidirectional"))
      (node (ref "T101") (pin "2") (pinfunction "2_2") (pintype "bidirectional"))
      (node (ref "U101") (pin "1") (pinfunction "VIN_1") (pintype "bidirectional"))
      (node (ref "U203") (pin "1") (pinfunction "VIN_1") (pintype "power_in"))
    )
    (net (code "62") (name "VCC_HV") (class "Default")
      (node (ref "C110") (pin "2") (pinfunction "2_2") (pintype "passive"))
      (node (ref "C111") (pin "1") (pinfunction "1_1") (pintype "passive"))
      (node (ref "C112") (pin "P") (pinfunction "+_P") (pintype "passive"))
      (node (ref "C113") (pin "P") (pinfunction "+_P") (pintype "passive"))
      (node (ref "C206") (pin "1") (pinfunction "1_1") (pintype "passive"))
      (node (ref "D103") (pin "C") (pinfunction "C_C") (pintype "passive"))
      (node (ref "J302") (pin "2") (pinfunction "2_2") (pintype "passive"))
      (node (ref "J303") (pin "1") (pinfunction "1_1") (pintype "passive"))
      (node (ref "R102") (pin "2") (pinfunction "2_2") (pintype "passive"))
      (node (ref "R103") (pin "2") (pinfunction "2_2") (pintype "passive"))
      (node (ref "R104") (pin "2") (pinfunction "2_2") (pintype "passive"))
      (node (ref "R211") (pin "2") (pinfunction "2_2") (pintype "passive"))
      (node (ref "R212") (pin "2") (pinfunction "2_2") (pintype "passive"))
      (node (ref "R213") (pin "1") (pinfunction "1_1") (pintype "passive"))
      (node (ref "R302") (pin "2") (pinfunction "2_2") (pintype "passive"))
    )
    (net (code "63") (name "VGATE_HV") (class "Default")
      (node (ref "C203") (pin "1") (pinfunction "1_1") (pintype "passive"))
      (node (ref "C204") (pin "1") (pinfunction "1_1") (pintype "passive"))
      (node (ref "C208") (pin "1") (pinfunction "1_1") (pintype "passive"))
      (node (ref "C301") (pin "1") (pinfunction "1_1") (pintype "passive"))
      (node (ref "OP201") (pin "4") (pinfunction "COL_4") (pintype "passive"))
      (node (ref "OP202") (pin "4") (pinfunction "COL_4") (pintype "passive"))
      (node (ref "R214") (pin "2") (pinfunction "2_2") (pintype "passive"))
      (node (ref "U201") (pin "P1") (pinfunction "EN_P1") (pintype "bidirectional"))
      (node (ref "U201") (pin "P3") (pinfunction "VDD_P3") (pintype "bidirectional"))
      (node (ref "U202") (pin "P1") (pinfunction "EN_P1") (pintype "bidirectional"))
      (node (ref "U202") (pin "P3") (pinfunction "VDD_P3") (pintype "bidirectional"))
      (node (ref "U301") (pin "6") (pinfunction "LDOIN_6") (pintype "power_in"))
    )
    (net (code "64") (name "unconnected-(H101-Pad1)") (class "Default")
      (node (ref "H101") (pin "1") (pinfunction "1_1") (pintype "passive"))
    )
    (net (code "65") (name "unconnected-(H102-Pad1)") (class "Default")
      (node (ref "H102") (pin "1") (pinfunction "1_1") (pintype "passive"))
    )
    (net (code "66") (name "unconnected-(H103-Pad1)") (class "Default")
      (node (ref "H103") (pin "1") (pinfunction "1_1") (pintype "passive"))
    )
    (net (code "67") (name "unconnected-(J301-8-Pad9)") (class "Default")
      (node (ref "J301") (pin "9") (pinfunction "8_9") (pintype "passive"))
    )
    (net (code "68") (name "unconnected-(J301-9-Pad8)") (class "Default")
      (node (ref "J301") (pin "8") (pinfunction "9_8") (pintype "passive"))
    )
    (net (code "69") (name "unconnected-(Y301-NC-PadP2)") (class "Default")
      (node (ref "Y301") (pin "P2") (pinfunction "NC_P2") (pintype "bidirectional"))
    )
  )
)
